# fishbotv0_1_2022-03-06.net
KiCad netlist of a schematic drawn in Altium Designer
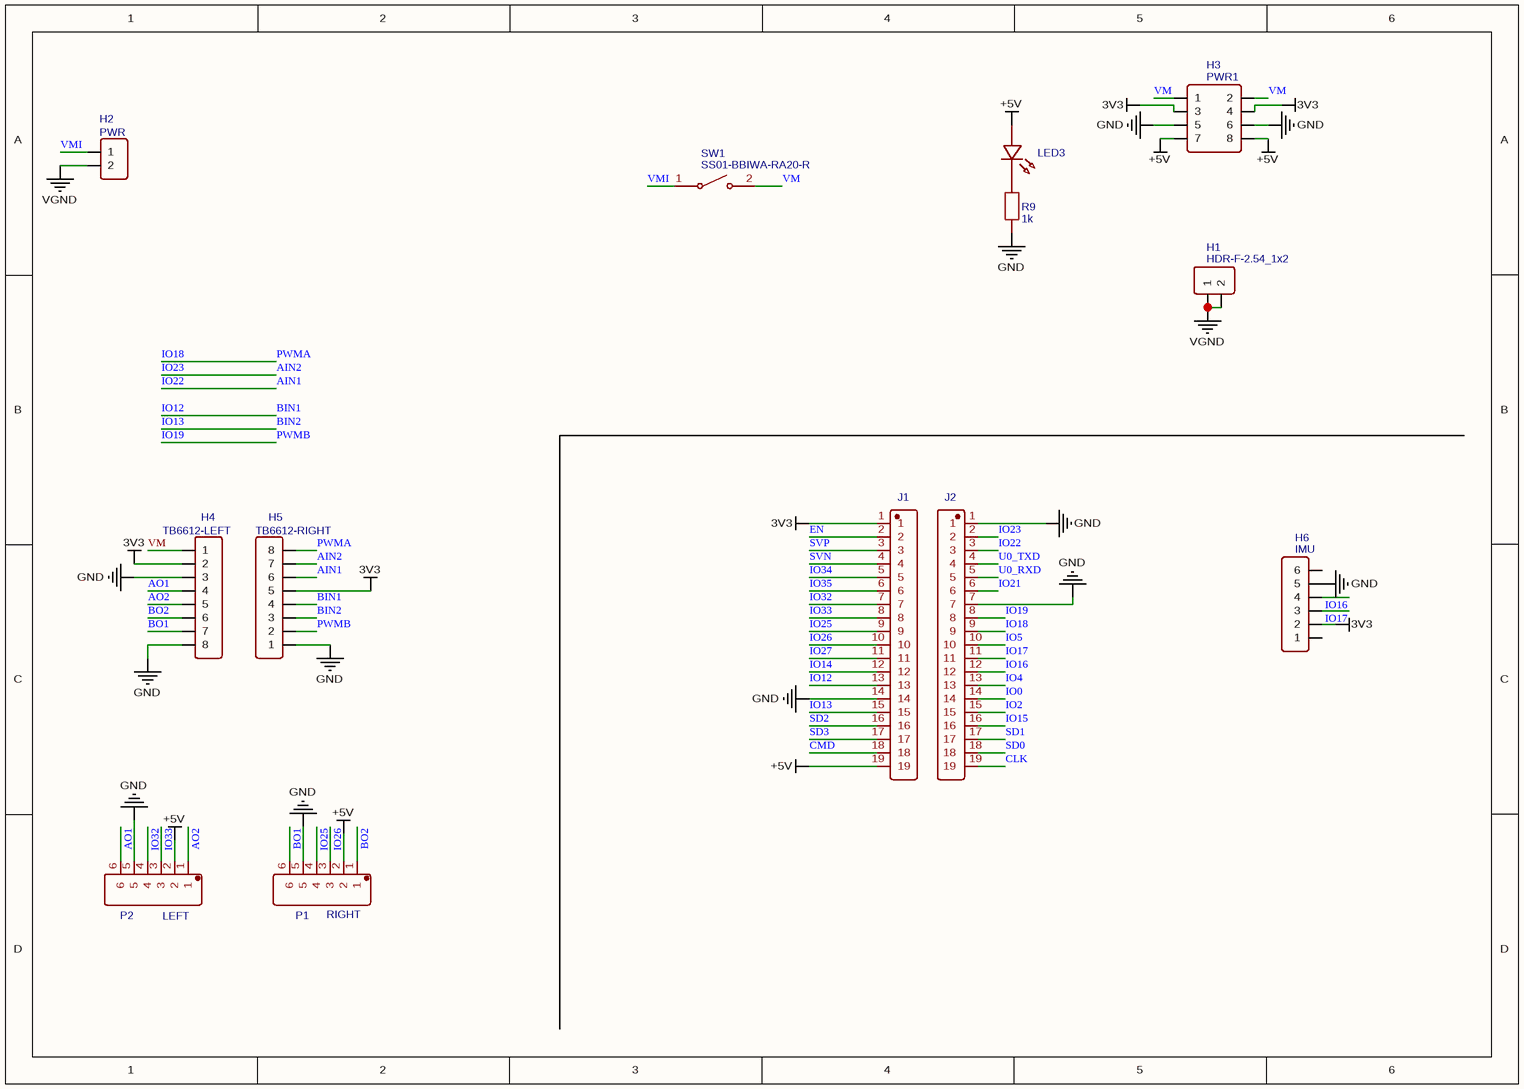
[diagram p0: fishbotv0.1_2022-03-06.schdoc]

(export (version "E")
  (design (tool "Eeschema 10.0.6"))
  (components
    (comp (ref "H1")
      (value "HDR-F-2.54_1x2")
      (fields (field (name "BOM_SUPPLIER PART") "C49661") (field (name "CONTRIBUTOR") "LCEDA_Lib"))
      (libsource (lib "altium-import") (part "root_1_HDR-F-2.54_1x2_"))
    )
    (comp (ref "H2")
      (value "PWR")
      (fields (field (name "BOM_SUPPLIER PART") "C49661") (field (name "CONTRIBUTOR") "LCEDA_Lib"))
      (libsource (lib "altium-import") (part "root_0_PWR_"))
    )
    (comp (ref "H3")
      (value "PWR1")
      (fields (field (name "BOM_SUPPLIER PART") "C239344") (field (name "CONTRIBUTOR") "LCEDA_Lib"))
      (libsource (lib "altium-import") (part "root_0_PWR1_"))
    )
    (comp (ref "H4")
      (value "TB6612-LEFT")
      (fields (field (name "BOM_SUPPLIER PART") "C225505") (field (name "CONTRIBUTOR") "LCEDA_Lib"))
      (libsource (lib "altium-import") (part "root_0_TB6612-LEFT_"))
    )
    (comp (ref "H5")
      (value "TB6612-RIGHT")
      (fields (field (name "BOM_SUPPLIER PART") "C225505") (field (name "CONTRIBUTOR") "LCEDA_Lib"))
      (libsource (lib "altium-import") (part "root_2_TB6612-RIGHT_"))
    )
    (comp (ref "H6")
      (value "IMU")
      (fields (field (name "BOM_SUPPLIER PART") "C40877") (field (name "CONTRIBUTOR") "LCEDA_Lib"))
      (libsource (lib "altium-import") (part "root_2_IMU_"))
    )
    (comp (ref "J1")
      (value "Header-Male-2.54_1x19")
      (fields
        (field (name "BOM_MANUFACTURER PART") "2.54mm 1*20PHeader")
        (field (name "BOM_SUPPLIER PART") "C50981")
        (field (name "CONTRIBUTOR") "shiyindebcd")
      )
      (libsource (lib "altium-import") (part "root_0_Header-Male-2.54_1x19_"))
    )
    (comp (ref "J2")
      (value "Header-Male-2.54_1x19")
      (fields
        (field (name "BOM_MANUFACTURER PART") "2.54mm 1*20PHeader")
        (field (name "BOM_SUPPLIER PART") "C50981")
        (field (name "CONTRIBUTOR") "shiyindebcd")
      )
      (libsource (lib "") (part "root_0_Header-Male-2.54_1x19__1"))
    )
    (comp (ref "LED3")
      (value "LED-0603_R")
      (fields
        (field (name "BOM_MANUFACTURER PART") "19-217/R6C-AL1M2VY/3T")
        (field (name "BOM_SUPPLIER PART") "C72044")
        (field (name "CONTRIBUTOR") "LCEDA_01")
      )
      (libsource (lib "altium-import") (part "root_3_LED-0603_R_"))
    )
    (comp (ref "P1")
      (value "RIGHT")
      (fields
        (field (name "BOM_MANUFACTURER PART") "2.54pitch 6P")
        (field (name "BOM_SUPPLIER PART") "C24361")
      )
      (libsource (lib "altium-import") (part "root_3_RIGHT_"))
    )
    (comp (ref "P2")
      (value "LEFT")
      (fields
        (field (name "BOM_MANUFACTURER PART") "2.54pitch 6P")
        (field (name "BOM_SUPPLIER PART") "C24361")
      )
      (libsource (lib "altium-import") (part "root_3_LEFT_"))
    )
    (comp (ref "R9")
      (value "1k")
      (fields (field (name "CONTRIBUTOR") "LCEDA_Lib"))
      (libsource (lib "altium-import") (part "root_3_1k_"))
    )
    (comp (ref "SW1")
      (value "SS01-BBIWA-RA20-R")
      (fields (field (name "BOM_SUPPLIER PART") "C309065") (field (name "CONTRIBUTOR") "LCSC"))
      (libsource (lib "altium-import") (part "root_0_SS01-BBIWA-RA20-R_"))
    )
  )
  (nets
    (net (code "1") (name "+5V") (class "Default")
      (node (ref "H3") (pin "7") (pinfunction "7_7") (pintype "passive"))
      (node (ref "H3") (pin "8") (pinfunction "8_8") (pintype "passive"))
      (node (ref "J1") (pin "19") (pinfunction "19_19") (pintype "passive"))
      (node (ref "LED3") (pin "1") (pinfunction "1_1") (pintype "passive"))
      (node (ref "P1") (pin "2") (pinfunction "2_2") (pintype "passive"))
      (node (ref "P2") (pin "2") (pinfunction "2_2") (pintype "passive"))
    )
    (net (code "2") (name "/AIN1") (class "Default")
      (node (ref "H5") (pin "6") (pinfunction "6_6") (pintype "passive"))
      (node (ref "J2") (pin "3") (pinfunction "3_3") (pintype "passive"))
    )
    (net (code "3") (name "/AIN2") (class "Default")
      (node (ref "H5") (pin "7") (pinfunction "7_7") (pintype "passive"))
      (node (ref "J2") (pin "2") (pinfunction "2_2") (pintype "passive"))
    )
    (net (code "4") (name "/AO1") (class "Default")
      (node (ref "H4") (pin "4") (pinfunction "4_4") (pintype "passive"))
      (node (ref "P2") (pin "6") (pinfunction "6_6") (pintype "passive"))
    )
    (net (code "5") (name "/AO2") (class "Default")
      (node (ref "H4") (pin "5") (pinfunction "5_5") (pintype "passive"))
      (node (ref "P2") (pin "1") (pinfunction "1_1") (pintype "passive"))
    )
    (net (code "6") (name "/BIN1") (class "Default")
      (node (ref "H5") (pin "4") (pinfunction "4_4") (pintype "passive"))
      (node (ref "J1") (pin "13") (pinfunction "13_13") (pintype "passive"))
    )
    (net (code "7") (name "/BIN2") (class "Default")
      (node (ref "H5") (pin "3") (pinfunction "3_3") (pintype "passive"))
      (node (ref "J1") (pin "15") (pinfunction "15_15") (pintype "passive"))
    )
    (net (code "8") (name "/BO1") (class "Default")
      (node (ref "H4") (pin "7") (pinfunction "7_7") (pintype "passive"))
      (node (ref "P1") (pin "6") (pinfunction "6_6") (pintype "passive"))
    )
    (net (code "9") (name "/BO2") (class "Default")
      (node (ref "H4") (pin "6") (pinfunction "6_6") (pintype "passive"))
      (node (ref "P1") (pin "1") (pinfunction "1_1") (pintype "passive"))
    )
    (net (code "10") (name "/CLK") (class "Default")
      (node (ref "J2") (pin "19") (pinfunction "19_19") (pintype "passive"))
    )
    (net (code "11") (name "/CMD") (class "Default")
      (node (ref "J1") (pin "18") (pinfunction "18_18") (pintype "passive"))
    )
    (net (code "12") (name "/EN") (class "Default")
      (node (ref "J1") (pin "2") (pinfunction "2_2") (pintype "passive"))
    )
    (net (code "13") (name "/IO0") (class "Default")
      (node (ref "J2") (pin "14") (pinfunction "14_14") (pintype "passive"))
    )
    (net (code "14") (name "/IO2") (class "Default")
      (node (ref "J2") (pin "15") (pinfunction "15_15") (pintype "passive"))
    )
    (net (code "15") (name "/IO4") (class "Default")
      (node (ref "J2") (pin "13") (pinfunction "13_13") (pintype "passive"))
    )
    (net (code "16") (name "/IO5") (class "Default")
      (node (ref "J2") (pin "10") (pinfunction "10_10") (pintype "passive"))
    )
    (net (code "17") (name "/IO14") (class "Default")
      (node (ref "J1") (pin "12") (pinfunction "12_12") (pintype "passive"))
    )
    (net (code "18") (name "/IO15") (class "Default")
      (node (ref "J2") (pin "16") (pinfunction "16_16") (pintype "passive"))
    )
    (net (code "19") (name "/IO16") (class "Default")
      (node (ref "H6") (pin "4") (pinfunction "4_4") (pintype "passive"))
      (node (ref "J2") (pin "12") (pinfunction "12_12") (pintype "passive"))
    )
    (net (code "20") (name "/IO17") (class "Default")
      (node (ref "H6") (pin "3") (pinfunction "3_3") (pintype "passive"))
      (node (ref "J2") (pin "11") (pinfunction "11_11") (pintype "passive"))
    )
    (net (code "21") (name "/IO18") (class "Default")
      (node (ref "H5") (pin "8") (pinfunction "8_8") (pintype "passive"))
      (node (ref "J2") (pin "9") (pinfunction "9_9") (pintype "passive"))
    )
    (net (code "22") (name "/IO19") (class "Default")
      (node (ref "H5") (pin "2") (pinfunction "2_2") (pintype "passive"))
      (node (ref "J2") (pin "8") (pinfunction "8_8") (pintype "passive"))
    )
    (net (code "23") (name "/IO21") (class "Default")
      (node (ref "J2") (pin "6") (pinfunction "6_6") (pintype "passive"))
    )
    (net (code "24") (name "/IO25") (class "Default")
      (node (ref "J1") (pin "9") (pinfunction "9_9") (pintype "passive"))
      (node (ref "P1") (pin "4") (pinfunction "4_4") (pintype "passive"))
    )
    (net (code "25") (name "/IO26") (class "Default")
      (node (ref "J1") (pin "10") (pinfunction "10_10") (pintype "passive"))
      (node (ref "P1") (pin "3") (pinfunction "3_3") (pintype "passive"))
    )
    (net (code "26") (name "/IO27") (class "Default")
      (node (ref "J1") (pin "11") (pinfunction "11_11") (pintype "passive"))
    )
    (net (code "27") (name "/IO32") (class "Default")
      (node (ref "J1") (pin "7") (pinfunction "7_7") (pintype "passive"))
      (node (ref "P2") (pin "4") (pinfunction "4_4") (pintype "passive"))
    )
    (net (code "28") (name "/IO33") (class "Default")
      (node (ref "J1") (pin "8") (pinfunction "8_8") (pintype "passive"))
      (node (ref "P2") (pin "3") (pinfunction "3_3") (pintype "passive"))
    )
    (net (code "29") (name "/IO34") (class "Default")
      (node (ref "J1") (pin "5") (pinfunction "5_5") (pintype "passive"))
    )
    (net (code "30") (name "/IO35") (class "Default")
      (node (ref "J1") (pin "6") (pinfunction "6_6") (pintype "passive"))
    )
    (net (code "31") (name "/SD0") (class "Default")
      (node (ref "J2") (pin "18") (pinfunction "18_18") (pintype "passive"))
    )
    (net (code "32") (name "/SD1") (class "Default")
      (node (ref "J2") (pin "17") (pinfunction "17_17") (pintype "passive"))
    )
    (net (code "33") (name "/SD2") (class "Default")
      (node (ref "J1") (pin "16") (pinfunction "16_16") (pintype "passive"))
    )
    (net (code "34") (name "/SD3") (class "Default")
      (node (ref "J1") (pin "17") (pinfunction "17_17") (pintype "passive"))
    )
    (net (code "35") (name "/SVN") (class "Default")
      (node (ref "J1") (pin "4") (pinfunction "4_4") (pintype "passive"))
    )
    (net (code "36") (name "/SVP") (class "Default")
      (node (ref "J1") (pin "3") (pinfunction "3_3") (pintype "passive"))
    )
    (net (code "37") (name "/U0_RXD") (class "Default")
      (node (ref "J2") (pin "5") (pinfunction "5_5") (pintype "passive"))
    )
    (net (code "38") (name "/U0_TXD") (class "Default")
      (node (ref "J2") (pin "4") (pinfunction "4_4") (pintype "passive"))
    )
    (net (code "39") (name "/VM") (class "Default")
      (node (ref "H3") (pin "1") (pinfunction "1_1") (pintype "passive"))
      (node (ref "H3") (pin "2") (pinfunction "2_2") (pintype "passive"))
      (node (ref "H4") (pin "1") (pinfunction "1_1") (pintype "passive"))
      (node (ref "SW1") (pin "2") (pinfunction "2_2") (pintype "passive"))
    )
    (net (code "40") (name "/VMI") (class "Default")
      (node (ref "H2") (pin "1") (pinfunction "1_1") (pintype "passive"))
      (node (ref "SW1") (pin "1") (pinfunction "1_1") (pintype "passive"))
    )
    (net (code "41") (name "3V3") (class "Default")
      (node (ref "H3") (pin "3") (pinfunction "3_3") (pintype "passive"))
      (node (ref "H3") (pin "4") (pinfunction "4_4") (pintype "passive"))
      (node (ref "H4") (pin "2") (pinfunction "2_2") (pintype "passive"))
      (node (ref "H5") (pin "5") (pinfunction "5_5") (pintype "passive"))
      (node (ref "H6") (pin "2") (pinfunction "2_2") (pintype "passive"))
      (node (ref "J1") (pin "1") (pinfunction "1_1") (pintype "passive"))
    )
    (net (code "42") (name "GND") (class "Default")
      (node (ref "H3") (pin "5") (pinfunction "5_5") (pintype "passive"))
      (node (ref "H3") (pin "6") (pinfunction "6_6") (pintype "passive"))
      (node (ref "H4") (pin "3") (pinfunction "3_3") (pintype "passive"))
      (node (ref "H4") (pin "8") (pinfunction "8_8") (pintype "passive"))
      (node (ref "H5") (pin "1") (pinfunction "1_1") (pintype "passive"))
      (node (ref "H6") (pin "5") (pinfunction "5_5") (pintype "passive"))
      (node (ref "J1") (pin "14") (pinfunction "14_14") (pintype "passive"))
      (node (ref "J2") (pin "1") (pinfunction "1_1") (pintype "passive"))
      (node (ref "J2") (pin "7") (pinfunction "7_7") (pintype "passive"))
      (node (ref "P1") (pin "5") (pinfunction "5_5") (pintype "passive"))
      (node (ref "P2") (pin "5") (pinfunction "5_5") (pintype "passive"))
      (node (ref "R9") (pin "2") (pinfunction "2_2") (pintype "passive"))
    )
    (net (code "43") (name "Net-(LED3-Pad2)") (class "Default")
      (node (ref "LED3") (pin "2") (pinfunction "2_2") (pintype "passive"))
      (node (ref "R9") (pin "1") (pinfunction "1_1") (pintype "passive"))
    )
    (net (code "44") (name "VGND") (class "Default")
      (node (ref "H1") (pin "1") (pinfunction "1_1") (pintype "passive"))
      (node (ref "H1") (pin "2") (pinfunction "2_2") (pintype "passive"))
      (node (ref "H2") (pin "2") (pinfunction "2_2") (pintype "passive"))
    )
    (net (code "45") (name "unconnected-(H6-Pad1)") (class "Default")
      (node (ref "H6") (pin "1") (pinfunction "1_1") (pintype "passive"))
    )
    (net (code "46") (name "unconnected-(H6-Pad6)") (class "Default")
      (node (ref "H6") (pin "6") (pinfunction "6_6") (pintype "passive"))
    )
  )
)
